# IMU.net
KiCad netlist of a schematic drawn in EAGLE
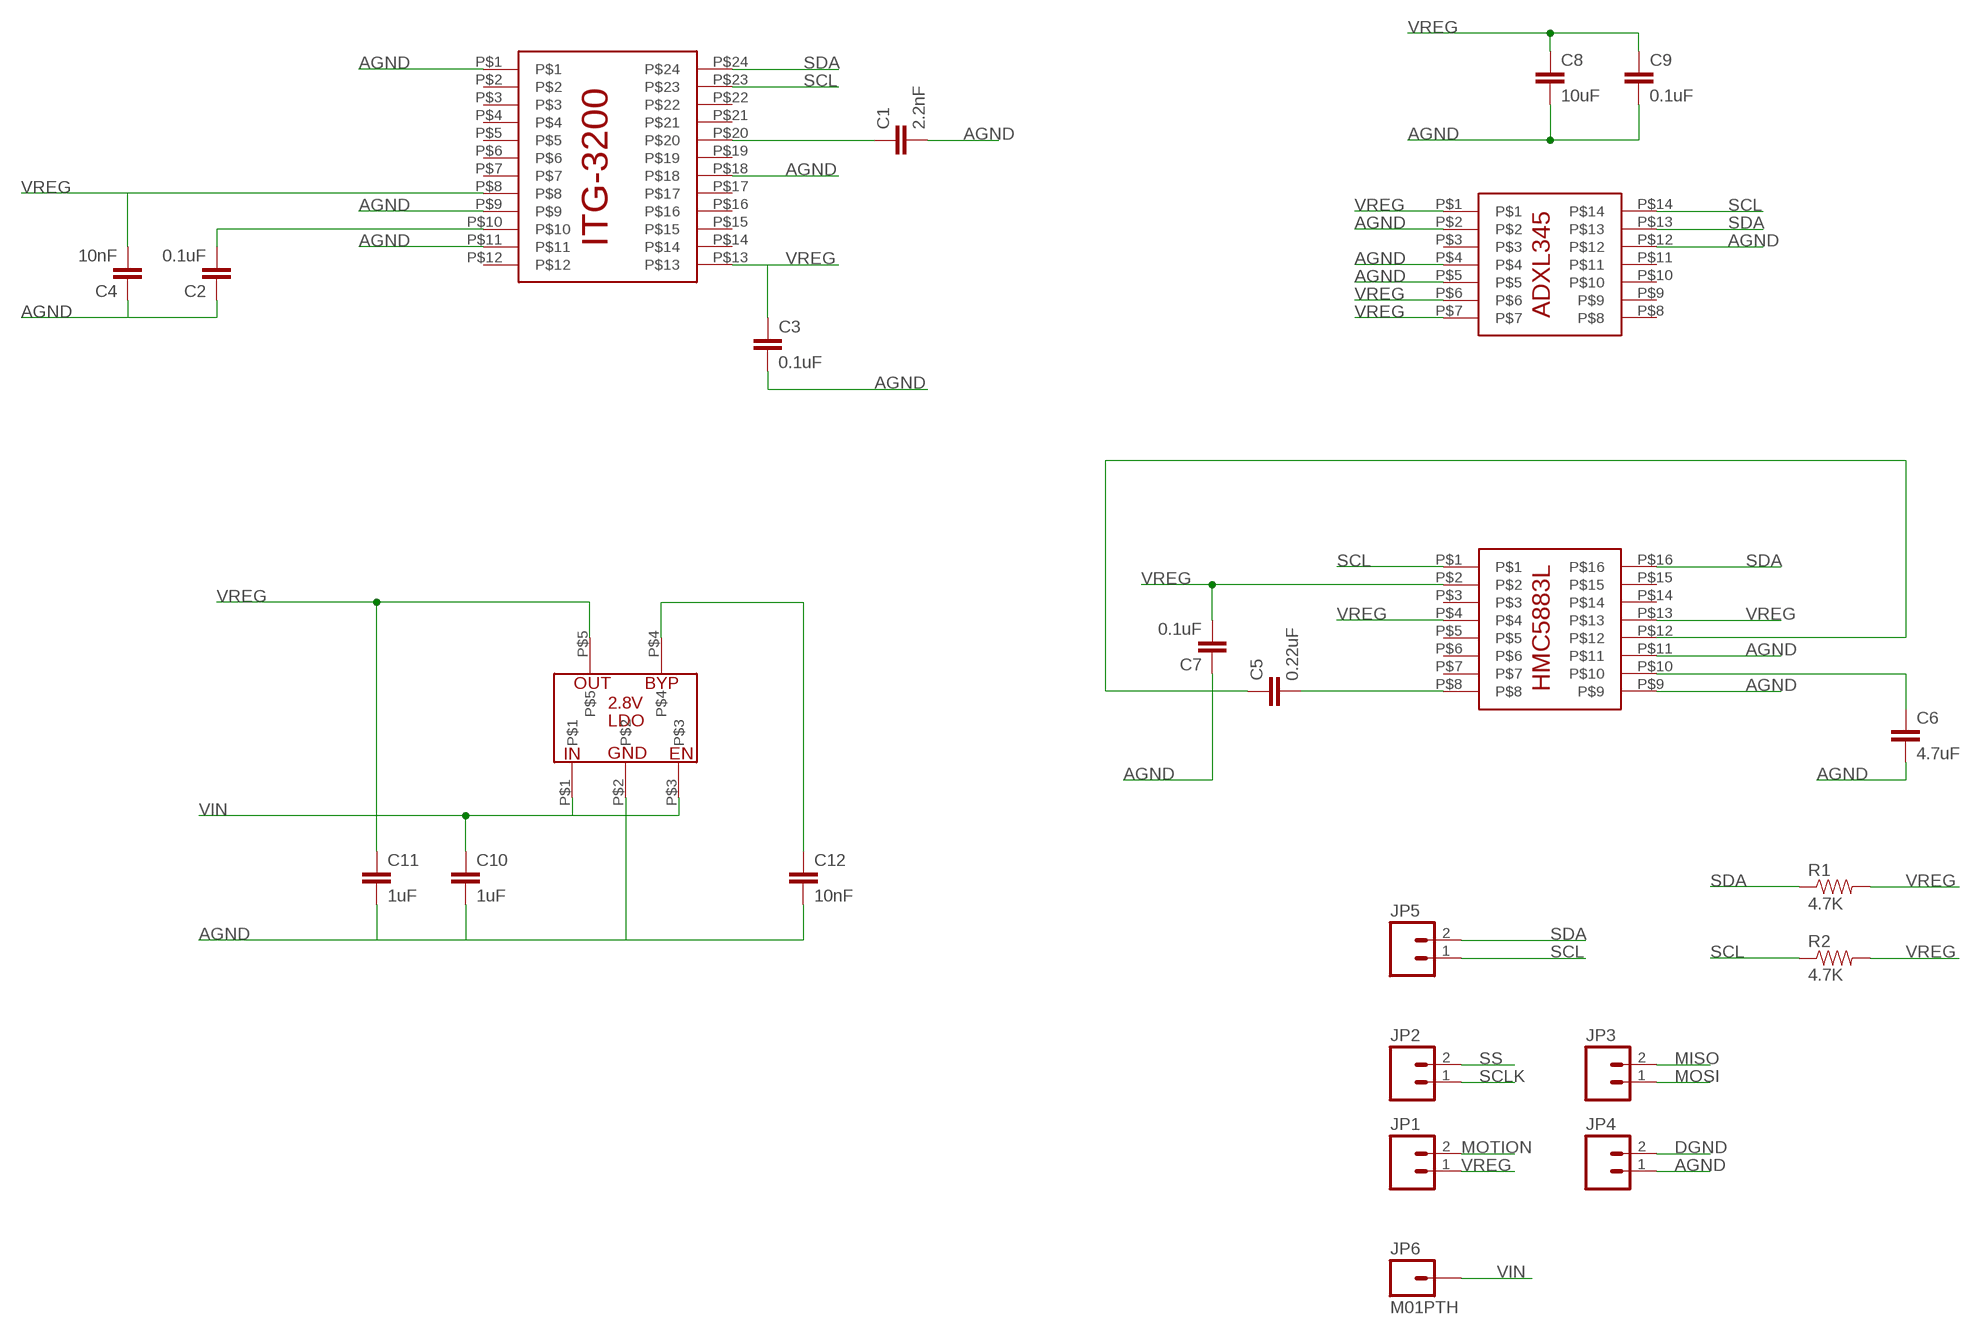
[diagram p0: schematic, sheet 1]

(export (version "E")
  (design (tool "Eeschema 10.0.6"))
  (components
    (comp (ref "C1")
      (value "2.2nF")
      (footprint "eagle-import:0603-CAP")
      (libsource (lib "eagle-import") (part "CAP0603-CAP"))
    )
    (comp (ref "C2")
      (value "0.1uF")
      (footprint "eagle-import:0603-CAP")
      (libsource (lib "eagle-import") (part "CAP0603-CAP"))
    )
    (comp (ref "C3")
      (value "0.1uF")
      (footprint "eagle-import:0603-CAP")
      (libsource (lib "eagle-import") (part "CAP0603-CAP"))
    )
    (comp (ref "C4")
      (value "10nF")
      (footprint "eagle-import:0603-CAP")
      (libsource (lib "eagle-import") (part "CAP0603-CAP"))
    )
    (comp (ref "C5")
      (value "0.22uF")
      (footprint "eagle-import:0603-CAP")
      (libsource (lib "eagle-import") (part "CAP0603-CAP"))
    )
    (comp (ref "C6")
      (value "4.7uF")
      (footprint "eagle-import:0603-CAP")
      (libsource (lib "eagle-import") (part "CAP0603-CAP"))
    )
    (comp (ref "C7")
      (value "0.1uF")
      (footprint "eagle-import:0603-CAP")
      (libsource (lib "eagle-import") (part "CAP0603-CAP"))
    )
    (comp (ref "C8")
      (value "10uF")
      (footprint "eagle-import:0603-CAP")
      (libsource (lib "eagle-import") (part "CAP0603-CAP"))
    )
    (comp (ref "C9")
      (value "0.1uF")
      (footprint "eagle-import:0603-CAP")
      (libsource (lib "eagle-import") (part "CAP0603-CAP"))
    )
    (comp (ref "C10")
      (value "1uF")
      (footprint "eagle-import:0603-CAP")
      (libsource (lib "eagle-import") (part "CAP0603-CAP"))
    )
    (comp (ref "C11")
      (value "1uF")
      (footprint "eagle-import:0603-CAP")
      (libsource (lib "eagle-import") (part "CAP0603-CAP"))
    )
    (comp (ref "C12")
      (value "10nF")
      (footprint "eagle-import:0603-CAP")
      (libsource (lib "eagle-import") (part "CAP0603-CAP"))
    )
    (comp (ref "JP1")
      (value "M02PTH")
      (footprint "eagle-import:1X02")
      (libsource (lib "eagle-import") (part "M02PTH"))
    )
    (comp (ref "JP2")
      (value "M02PTH")
      (footprint "eagle-import:1X02")
      (libsource (lib "eagle-import") (part "M02PTH"))
    )
    (comp (ref "JP3")
      (value "M02PTH")
      (footprint "eagle-import:1X02")
      (libsource (lib "eagle-import") (part "M02PTH"))
    )
    (comp (ref "JP4")
      (value "M02PTH")
      (footprint "eagle-import:1X02")
      (libsource (lib "eagle-import") (part "M02PTH"))
    )
    (comp (ref "JP5")
      (value "M02PTH")
      (footprint "eagle-import:1X02")
      (libsource (lib "eagle-import") (part "M02PTH"))
    )
    (comp (ref "JP6")
      (value "M01PTH")
      (footprint "eagle-import:1X01")
      (libsource (lib "eagle-import") (part "M01PTH"))
    )
    (comp (ref "R1")
      (value "4.7K")
      (footprint "eagle-import:0603-RES")
      (libsource (lib "eagle-import") (part "RESISTOR0603-RES"))
    )
    (comp (ref "R2")
      (value "4.7K")
      (footprint "eagle-import:0603-RES")
      (libsource (lib "eagle-import") (part "RESISTOR0603-RES"))
    )
    (comp (ref "U$2")
      (value "ADXL345")
      (footprint "eagle-import:ADXL345")
      (libsource (lib "eagle-import") (part "ADXL345"))
    )
    (comp (ref "U$3")
      (value "HMC5883L")
      (footprint "eagle-import:HMC5883L")
      (libsource (lib "eagle-import") (part "HMC5883L"))
    )
    (comp (ref "U$4")
      (value "ITG-3200")
      (footprint "eagle-import:ITG-3200")
      (libsource (lib "eagle-import") (part "ITG-3200"))
    )
    (comp (ref "U$5")
      (value "NCP700BMT28TBG__2.8V_LDO")
      (footprint "eagle-import:NCP700BMT28TBG__2.8V_LDO")
      (libsource (lib "eagle-import") (part "NCP700BMT28TBG__2.8V_LDO"))
    )
  )
  (nets
    (net (code "1") (name "/AGND") (class "Default")
      (node (ref "C1") (pin "2") (pinfunction "2_2") (pintype "passive"))
      (node (ref "C10") (pin "2") (pinfunction "2_2") (pintype "passive"))
      (node (ref "C11") (pin "2") (pinfunction "2_2") (pintype "passive"))
      (node (ref "C12") (pin "2") (pinfunction "2_2") (pintype "passive"))
      (node (ref "C2") (pin "1") (pinfunction "1_1") (pintype "passive"))
      (node (ref "C3") (pin "2") (pinfunction "2_2") (pintype "passive"))
      (node (ref "C4") (pin "1") (pinfunction "1_1") (pintype "passive"))
      (node (ref "C6") (pin "2") (pinfunction "2_2") (pintype "passive"))
      (node (ref "C7") (pin "1") (pinfunction "1_1") (pintype "passive"))
      (node (ref "C8") (pin "2") (pinfunction "2_2") (pintype "passive"))
      (node (ref "C9") (pin "2") (pinfunction "2_2") (pintype "passive"))
      (node (ref "JP4") (pin "1") (pinfunction "1_1") (pintype "passive"))
      (node (ref "U$2") (pin "P$12") (pinfunction "P$12_P$12") (pintype "bidirectional"))
      (node (ref "U$2") (pin "P$2") (pinfunction "P$2_P$2") (pintype "bidirectional"))
      (node (ref "U$2") (pin "P$4") (pinfunction "P$4_P$4") (pintype "bidirectional"))
      (node (ref "U$2") (pin "P$5") (pinfunction "P$5_P$5") (pintype "bidirectional"))
      (node (ref "U$3") (pin "P$11") (pinfunction "P$11_P$11") (pintype "bidirectional"))
      (node (ref "U$3") (pin "P$9") (pinfunction "P$9_P$9") (pintype "bidirectional"))
      (node (ref "U$4") (pin "P$1") (pinfunction "P$1_P$1") (pintype "bidirectional"))
      (node (ref "U$4") (pin "P$11") (pinfunction "P$11_P$11") (pintype "bidirectional"))
      (node (ref "U$4") (pin "P$18") (pinfunction "P$18_P$18") (pintype "bidirectional"))
      (node (ref "U$4") (pin "P$9") (pinfunction "P$9_P$9") (pintype "bidirectional"))
      (node (ref "U$5") (pin "P$2") (pinfunction "P$2_P$2") (pintype "bidirectional"))
    )
    (net (code "2") (name "/DGND") (class "Default")
      (node (ref "JP4") (pin "2") (pinfunction "2_2") (pintype "passive"))
    )
    (net (code "3") (name "/MISO") (class "Default")
      (node (ref "JP3") (pin "2") (pinfunction "2_2") (pintype "passive"))
    )
    (net (code "4") (name "/MOSI") (class "Default")
      (node (ref "JP3") (pin "1") (pinfunction "1_1") (pintype "passive"))
    )
    (net (code "5") (name "/MOTION") (class "Default")
      (node (ref "JP1") (pin "2") (pinfunction "2_2") (pintype "passive"))
    )
    (net (code "6") (name "/SCL") (class "Default")
      (node (ref "JP5") (pin "1") (pinfunction "1_1") (pintype "passive"))
      (node (ref "R2") (pin "1") (pinfunction "1_1") (pintype "passive"))
      (node (ref "U$2") (pin "P$14") (pinfunction "P$14_P$14") (pintype "bidirectional"))
      (node (ref "U$3") (pin "P$1") (pinfunction "P$1_P$1") (pintype "bidirectional"))
      (node (ref "U$4") (pin "P$23") (pinfunction "P$23_P$23") (pintype "bidirectional"))
    )
    (net (code "7") (name "/SCLK") (class "Default")
      (node (ref "JP2") (pin "1") (pinfunction "1_1") (pintype "passive"))
    )
    (net (code "8") (name "/SDA") (class "Default")
      (node (ref "JP5") (pin "2") (pinfunction "2_2") (pintype "passive"))
      (node (ref "R1") (pin "1") (pinfunction "1_1") (pintype "passive"))
      (node (ref "U$2") (pin "P$13") (pinfunction "P$13_P$13") (pintype "bidirectional"))
      (node (ref "U$3") (pin "P$16") (pinfunction "P$16_P$16") (pintype "bidirectional"))
      (node (ref "U$4") (pin "P$24") (pinfunction "P$24_P$24") (pintype "bidirectional"))
    )
    (net (code "9") (name "/SS") (class "Default")
      (node (ref "JP2") (pin "2") (pinfunction "2_2") (pintype "passive"))
    )
    (net (code "10") (name "/VIN") (class "Default")
      (node (ref "C10") (pin "1") (pinfunction "1_1") (pintype "passive"))
      (node (ref "JP6") (pin "1") (pinfunction "1_1") (pintype "passive"))
      (node (ref "U$5") (pin "P$1") (pinfunction "P$1_P$1") (pintype "bidirectional"))
      (node (ref "U$5") (pin "P$3") (pinfunction "P$3_P$3") (pintype "bidirectional"))
    )
    (net (code "11") (name "/VREG") (class "Default")
      (node (ref "C11") (pin "1") (pinfunction "1_1") (pintype "passive"))
      (node (ref "C3") (pin "1") (pinfunction "1_1") (pintype "passive"))
      (node (ref "C4") (pin "2") (pinfunction "2_2") (pintype "passive"))
      (node (ref "C7") (pin "2") (pinfunction "2_2") (pintype "passive"))
      (node (ref "C8") (pin "1") (pinfunction "1_1") (pintype "passive"))
      (node (ref "C9") (pin "1") (pinfunction "1_1") (pintype "passive"))
      (node (ref "JP1") (pin "1") (pinfunction "1_1") (pintype "passive"))
      (node (ref "R1") (pin "2") (pinfunction "2_2") (pintype "passive"))
      (node (ref "R2") (pin "2") (pinfunction "2_2") (pintype "passive"))
      (node (ref "U$2") (pin "P$1") (pinfunction "P$1_P$1") (pintype "bidirectional"))
      (node (ref "U$2") (pin "P$6") (pinfunction "P$6_P$6") (pintype "bidirectional"))
      (node (ref "U$2") (pin "P$7") (pinfunction "P$7_P$7") (pintype "bidirectional"))
      (node (ref "U$3") (pin "P$13") (pinfunction "P$13_P$13") (pintype "bidirectional"))
      (node (ref "U$3") (pin "P$2") (pinfunction "P$2_P$2") (pintype "bidirectional"))
      (node (ref "U$3") (pin "P$4") (pinfunction "P$4_P$4") (pintype "bidirectional"))
      (node (ref "U$4") (pin "P$13") (pinfunction "P$13_P$13") (pintype "bidirectional"))
      (node (ref "U$4") (pin "P$8") (pinfunction "P$8_P$8") (pintype "bidirectional"))
      (node (ref "U$5") (pin "P$5") (pinfunction "P$5_P$5") (pintype "bidirectional"))
    )
    (net (code "12") (name "Net-(C1-Pad1)") (class "Default")
      (node (ref "C1") (pin "1") (pinfunction "1_1") (pintype "passive"))
      (node (ref "U$4") (pin "P$20") (pinfunction "P$20_P$20") (pintype "bidirectional"))
    )
    (net (code "13") (name "Net-(C2-Pad2)") (class "Default")
      (node (ref "C2") (pin "2") (pinfunction "2_2") (pintype "passive"))
      (node (ref "U$4") (pin "P$10") (pinfunction "P$10_P$10") (pintype "bidirectional"))
    )
    (net (code "14") (name "Net-(C5-Pad1)") (class "Default")
      (node (ref "C5") (pin "1") (pinfunction "1_1") (pintype "passive"))
      (node (ref "U$3") (pin "P$12") (pinfunction "P$12_P$12") (pintype "bidirectional"))
    )
    (net (code "15") (name "Net-(C5-Pad2)") (class "Default")
      (node (ref "C5") (pin "2") (pinfunction "2_2") (pintype "passive"))
      (node (ref "U$3") (pin "P$8") (pinfunction "P$8_P$8") (pintype "bidirectional"))
    )
    (net (code "16") (name "Net-(C6-Pad1)") (class "Default")
      (node (ref "C6") (pin "1") (pinfunction "1_1") (pintype "passive"))
      (node (ref "U$3") (pin "P$10") (pinfunction "P$10_P$10") (pintype "bidirectional"))
    )
    (net (code "17") (name "Net-(C12-Pad1)") (class "Default")
      (node (ref "C12") (pin "1") (pinfunction "1_1") (pintype "passive"))
      (node (ref "U$5") (pin "P$4") (pinfunction "P$4_P$4") (pintype "bidirectional"))
    )
    (net (code "18") (name "unconnected-(U$2-PadP$3)") (class "Default")
      (node (ref "U$2") (pin "P$3") (pinfunction "P$3_P$3") (pintype "bidirectional"))
    )
    (net (code "19") (name "unconnected-(U$2-PadP$8)") (class "Default")
      (node (ref "U$2") (pin "P$8") (pinfunction "P$8_P$8") (pintype "bidirectional"))
    )
    (net (code "20") (name "unconnected-(U$2-PadP$9)") (class "Default")
      (node (ref "U$2") (pin "P$9") (pinfunction "P$9_P$9") (pintype "bidirectional"))
    )
    (net (code "21") (name "unconnected-(U$2-PadP$10)") (class "Default")
      (node (ref "U$2") (pin "P$10") (pinfunction "P$10_P$10") (pintype "bidirectional"))
    )
    (net (code "22") (name "unconnected-(U$2-PadP$11)") (class "Default")
      (node (ref "U$2") (pin "P$11") (pinfunction "P$11_P$11") (pintype "bidirectional"))
    )
    (net (code "23") (name "unconnected-(U$3-PadP$3)") (class "Default")
      (node (ref "U$3") (pin "P$3") (pinfunction "P$3_P$3") (pintype "bidirectional"))
    )
    (net (code "24") (name "unconnected-(U$3-PadP$5)") (class "Default")
      (node (ref "U$3") (pin "P$5") (pinfunction "P$5_P$5") (pintype "bidirectional"))
    )
    (net (code "25") (name "unconnected-(U$3-PadP$6)") (class "Default")
      (node (ref "U$3") (pin "P$6") (pinfunction "P$6_P$6") (pintype "bidirectional"))
    )
    (net (code "26") (name "unconnected-(U$3-PadP$7)") (class "Default")
      (node (ref "U$3") (pin "P$7") (pinfunction "P$7_P$7") (pintype "bidirectional"))
    )
    (net (code "27") (name "unconnected-(U$3-PadP$14)") (class "Default")
      (node (ref "U$3") (pin "P$14") (pinfunction "P$14_P$14") (pintype "bidirectional"))
    )
    (net (code "28") (name "unconnected-(U$3-PadP$15)") (class "Default")
      (node (ref "U$3") (pin "P$15") (pinfunction "P$15_P$15") (pintype "bidirectional"))
    )
    (net (code "29") (name "unconnected-(U$4-PadP$2)") (class "Default")
      (node (ref "U$4") (pin "P$2") (pinfunction "P$2_P$2") (pintype "bidirectional"))
    )
    (net (code "30") (name "unconnected-(U$4-PadP$3)") (class "Default")
      (node (ref "U$4") (pin "P$3") (pinfunction "P$3_P$3") (pintype "bidirectional"))
    )
    (net (code "31") (name "unconnected-(U$4-PadP$4)") (class "Default")
      (node (ref "U$4") (pin "P$4") (pinfunction "P$4_P$4") (pintype "bidirectional"))
    )
    (net (code "32") (name "unconnected-(U$4-PadP$5)") (class "Default")
      (node (ref "U$4") (pin "P$5") (pinfunction "P$5_P$5") (pintype "bidirectional"))
    )
    (net (code "33") (name "unconnected-(U$4-PadP$6)") (class "Default")
      (node (ref "U$4") (pin "P$6") (pinfunction "P$6_P$6") (pintype "bidirectional"))
    )
    (net (code "34") (name "unconnected-(U$4-PadP$7)") (class "Default")
      (node (ref "U$4") (pin "P$7") (pinfunction "P$7_P$7") (pintype "bidirectional"))
    )
    (net (code "35") (name "unconnected-(U$4-PadP$12)") (class "Default")
      (node (ref "U$4") (pin "P$12") (pinfunction "P$12_P$12") (pintype "bidirectional"))
    )
    (net (code "36") (name "unconnected-(U$4-PadP$14)") (class "Default")
      (node (ref "U$4") (pin "P$14") (pinfunction "P$14_P$14") (pintype "bidirectional"))
    )
    (net (code "37") (name "unconnected-(U$4-PadP$15)") (class "Default")
      (node (ref "U$4") (pin "P$15") (pinfunction "P$15_P$15") (pintype "bidirectional"))
    )
    (net (code "38") (name "unconnected-(U$4-PadP$16)") (class "Default")
      (node (ref "U$4") (pin "P$16") (pinfunction "P$16_P$16") (pintype "bidirectional"))
    )
    (net (code "39") (name "unconnected-(U$4-PadP$17)") (class "Default")
      (node (ref "U$4") (pin "P$17") (pinfunction "P$17_P$17") (pintype "bidirectional"))
    )
    (net (code "40") (name "unconnected-(U$4-PadP$19)") (class "Default")
      (node (ref "U$4") (pin "P$19") (pinfunction "P$19_P$19") (pintype "bidirectional"))
    )
    (net (code "41") (name "unconnected-(U$4-PadP$21)") (class "Default")
      (node (ref "U$4") (pin "P$21") (pinfunction "P$21_P$21") (pintype "bidirectional"))
    )
    (net (code "42") (name "unconnected-(U$4-PadP$22)") (class "Default")
      (node (ref "U$4") (pin "P$22") (pinfunction "P$22_P$22") (pintype "bidirectional"))
    )
  )
)
